# GateCircuit.net
KiCad netlist of a schematic drawn in Altium Designer
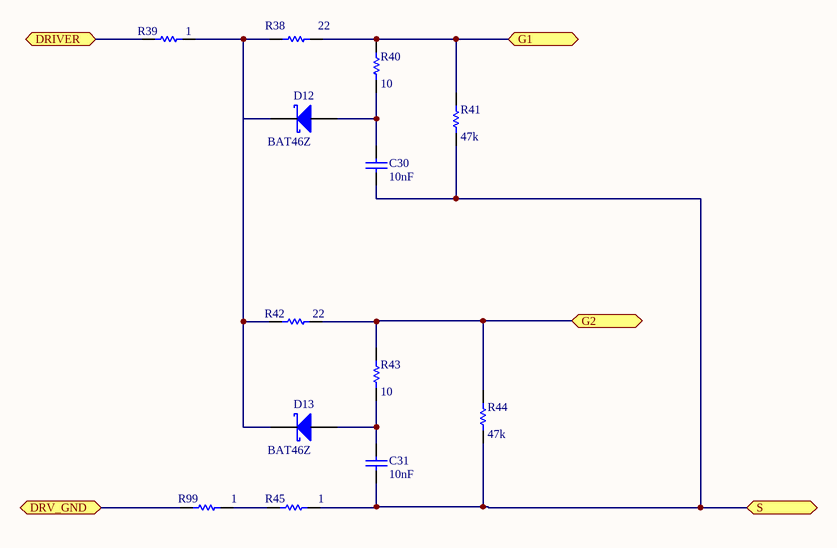
[diagram p0: GateCircuit.SchDoc]

(export (version "E")
  (design (tool "Eeschema 10.0.6"))
  (components
    (comp (ref "C30")
      (value "10nF")
      (footprint "0805_W")
      (description "Capacitor")
      (fields (field (name "PUBLISHER") "Altium Limited"))
      (libsource (lib "Inversor_LCEE") (part "Cap_0805"))
    )
    (comp (ref "C31")
      (value "10nF")
      (footprint "0805_W")
      (description "Capacitor")
      (fields (field (name "PUBLISHER") "Altium Limited"))
      (libsource (lib "Inversor_LCEE") (part "Cap_0805"))
    )
    (comp (ref "D12")
      (value "BAT46Z")
      (footprint "SOD-123")
      (description "Diodo Schottky")
      (libsource (lib "Sch_LCEE") (part "Schottky"))
    )
    (comp (ref "D13")
      (value "BAT46Z")
      (footprint "SOD-123")
      (description "Diodo Schottky")
      (libsource (lib "Sch_LCEE") (part "Schottky"))
    )
    (comp (ref "R38")
      (value "22")
      (footprint "1210_W")
      (description "Resistor")
      (fields
        (field (name "MANUFACTURER") "Generic Components")
        (field (name "PUBLISHER") "Altium Hobart Technology Centre")
      )
      (libsource (lib "Inversor_LCEE") (part "Res_0805"))
    )
    (comp (ref "R39")
      (value "1")
      (footprint "0805_W")
      (description "Resistor")
      (fields
        (field (name "MANUFACTURER") "Generic Components")
        (field (name "PUBLISHER") "Altium Hobart Technology Centre")
      )
      (libsource (lib "Inversor_LCEE") (part "Res_0805"))
    )
    (comp (ref "R40")
      (value "10")
      (footprint "0805_W")
      (description "Resistor")
      (fields
        (field (name "MANUFACTURER") "Generic Components")
        (field (name "PUBLISHER") "Altium Hobart Technology Centre")
      )
      (libsource (lib "Inversor_LCEE") (part "Res_0805"))
    )
    (comp (ref "R41")
      (value "47k")
      (footprint "0805_W")
      (description "Resistor")
      (fields
        (field (name "MANUFACTURER") "Generic Components")
        (field (name "PUBLISHER") "Altium Hobart Technology Centre")
      )
      (libsource (lib "Inversor_LCEE") (part "Res_0805"))
    )
    (comp (ref "R42")
      (value "22")
      (footprint "1210_W")
      (description "Resistor")
      (fields
        (field (name "MANUFACTURER") "Generic Components")
        (field (name "PUBLISHER") "Altium Hobart Technology Centre")
      )
      (libsource (lib "Inversor_LCEE") (part "Res_0805"))
    )
    (comp (ref "R43")
      (value "10")
      (footprint "0805_W")
      (description "Resistor")
      (fields
        (field (name "MANUFACTURER") "Generic Components")
        (field (name "PUBLISHER") "Altium Hobart Technology Centre")
      )
      (libsource (lib "Inversor_LCEE") (part "Res_0805"))
    )
    (comp (ref "R44")
      (value "47k")
      (footprint "0805_W")
      (description "Resistor")
      (fields
        (field (name "MANUFACTURER") "Generic Components")
        (field (name "PUBLISHER") "Altium Hobart Technology Centre")
      )
      (libsource (lib "Inversor_LCEE") (part "Res_0805"))
    )
    (comp (ref "R45")
      (value "1")
      (footprint "0805_W")
      (description "Resistor")
      (fields
        (field (name "MANUFACTURER") "Generic Components")
        (field (name "PUBLISHER") "Altium Hobart Technology Centre")
      )
      (libsource (lib "Inversor_LCEE") (part "Res_0805"))
    )
    (comp (ref "R99")
      (value "1")
      (footprint "0805_W")
      (description "Resistor")
      (fields
        (field (name "MANUFACTURER") "Generic Components")
        (field (name "PUBLISHER") "Altium Hobart Technology Centre")
      )
      (libsource (lib "Inversor_LCEE") (part "Res_0805"))
    )
  )
  (nets
    (net (code "1") (name "/DRIVER") (class "Default")
      (node (ref "R39") (pin "2") (pinfunction "2_2") (pintype "passive"))
    )
    (net (code "2") (name "/DRV_GND") (class "Default")
      (node (ref "R99") (pin "2") (pinfunction "2_2") (pintype "passive"))
    )
    (net (code "3") (name "/G1") (class "Default")
      (node (ref "R38") (pin "1") (pinfunction "1_1") (pintype "passive"))
      (node (ref "R40") (pin "1") (pinfunction "1_1") (pintype "passive"))
      (node (ref "R41") (pin "1") (pinfunction "1_1") (pintype "passive"))
    )
    (net (code "4") (name "/G2") (class "Default")
      (node (ref "R42") (pin "1") (pinfunction "1_1") (pintype "passive"))
      (node (ref "R43") (pin "1") (pinfunction "1_1") (pintype "passive"))
      (node (ref "R44") (pin "1") (pinfunction "1_1") (pintype "passive"))
    )
    (net (code "5") (name "/S") (class "Default")
      (node (ref "C30") (pin "1") (pinfunction "1_1") (pintype "passive"))
      (node (ref "C31") (pin "1") (pinfunction "1_1") (pintype "passive"))
      (node (ref "R41") (pin "2") (pinfunction "2_2") (pintype "passive"))
      (node (ref "R44") (pin "2") (pinfunction "2_2") (pintype "passive"))
      (node (ref "R45") (pin "1") (pinfunction "1_1") (pintype "passive"))
    )
    (net (code "6") (name "Net-(D12-A)") (class "Default")
      (node (ref "C30") (pin "2") (pinfunction "2_2") (pintype "passive"))
      (node (ref "D12") (pin "1") (pinfunction "A_1") (pintype "passive"))
      (node (ref "R40") (pin "2") (pinfunction "2_2") (pintype "passive"))
    )
    (net (code "7") (name "Net-(D12-K)") (class "Default")
      (node (ref "D12") (pin "2") (pinfunction "K_2") (pintype "passive"))
      (node (ref "D13") (pin "2") (pinfunction "K_2") (pintype "passive"))
      (node (ref "R38") (pin "2") (pinfunction "2_2") (pintype "passive"))
      (node (ref "R39") (pin "1") (pinfunction "1_1") (pintype "passive"))
      (node (ref "R42") (pin "2") (pinfunction "2_2") (pintype "passive"))
    )
    (net (code "8") (name "Net-(D13-A)") (class "Default")
      (node (ref "C31") (pin "2") (pinfunction "2_2") (pintype "passive"))
      (node (ref "D13") (pin "1") (pinfunction "A_1") (pintype "passive"))
      (node (ref "R43") (pin "2") (pinfunction "2_2") (pintype "passive"))
    )
    (net (code "9") (name "Net-(R45-Pad2)") (class "Default")
      (node (ref "R45") (pin "2") (pinfunction "2_2") (pintype "passive"))
      (node (ref "R99") (pin "1") (pinfunction "1_1") (pintype "passive"))
    )
  )
)
